# S1_LED_MAT_HDMI.net
KiCad netlist of a schematic drawn in Altium Designer
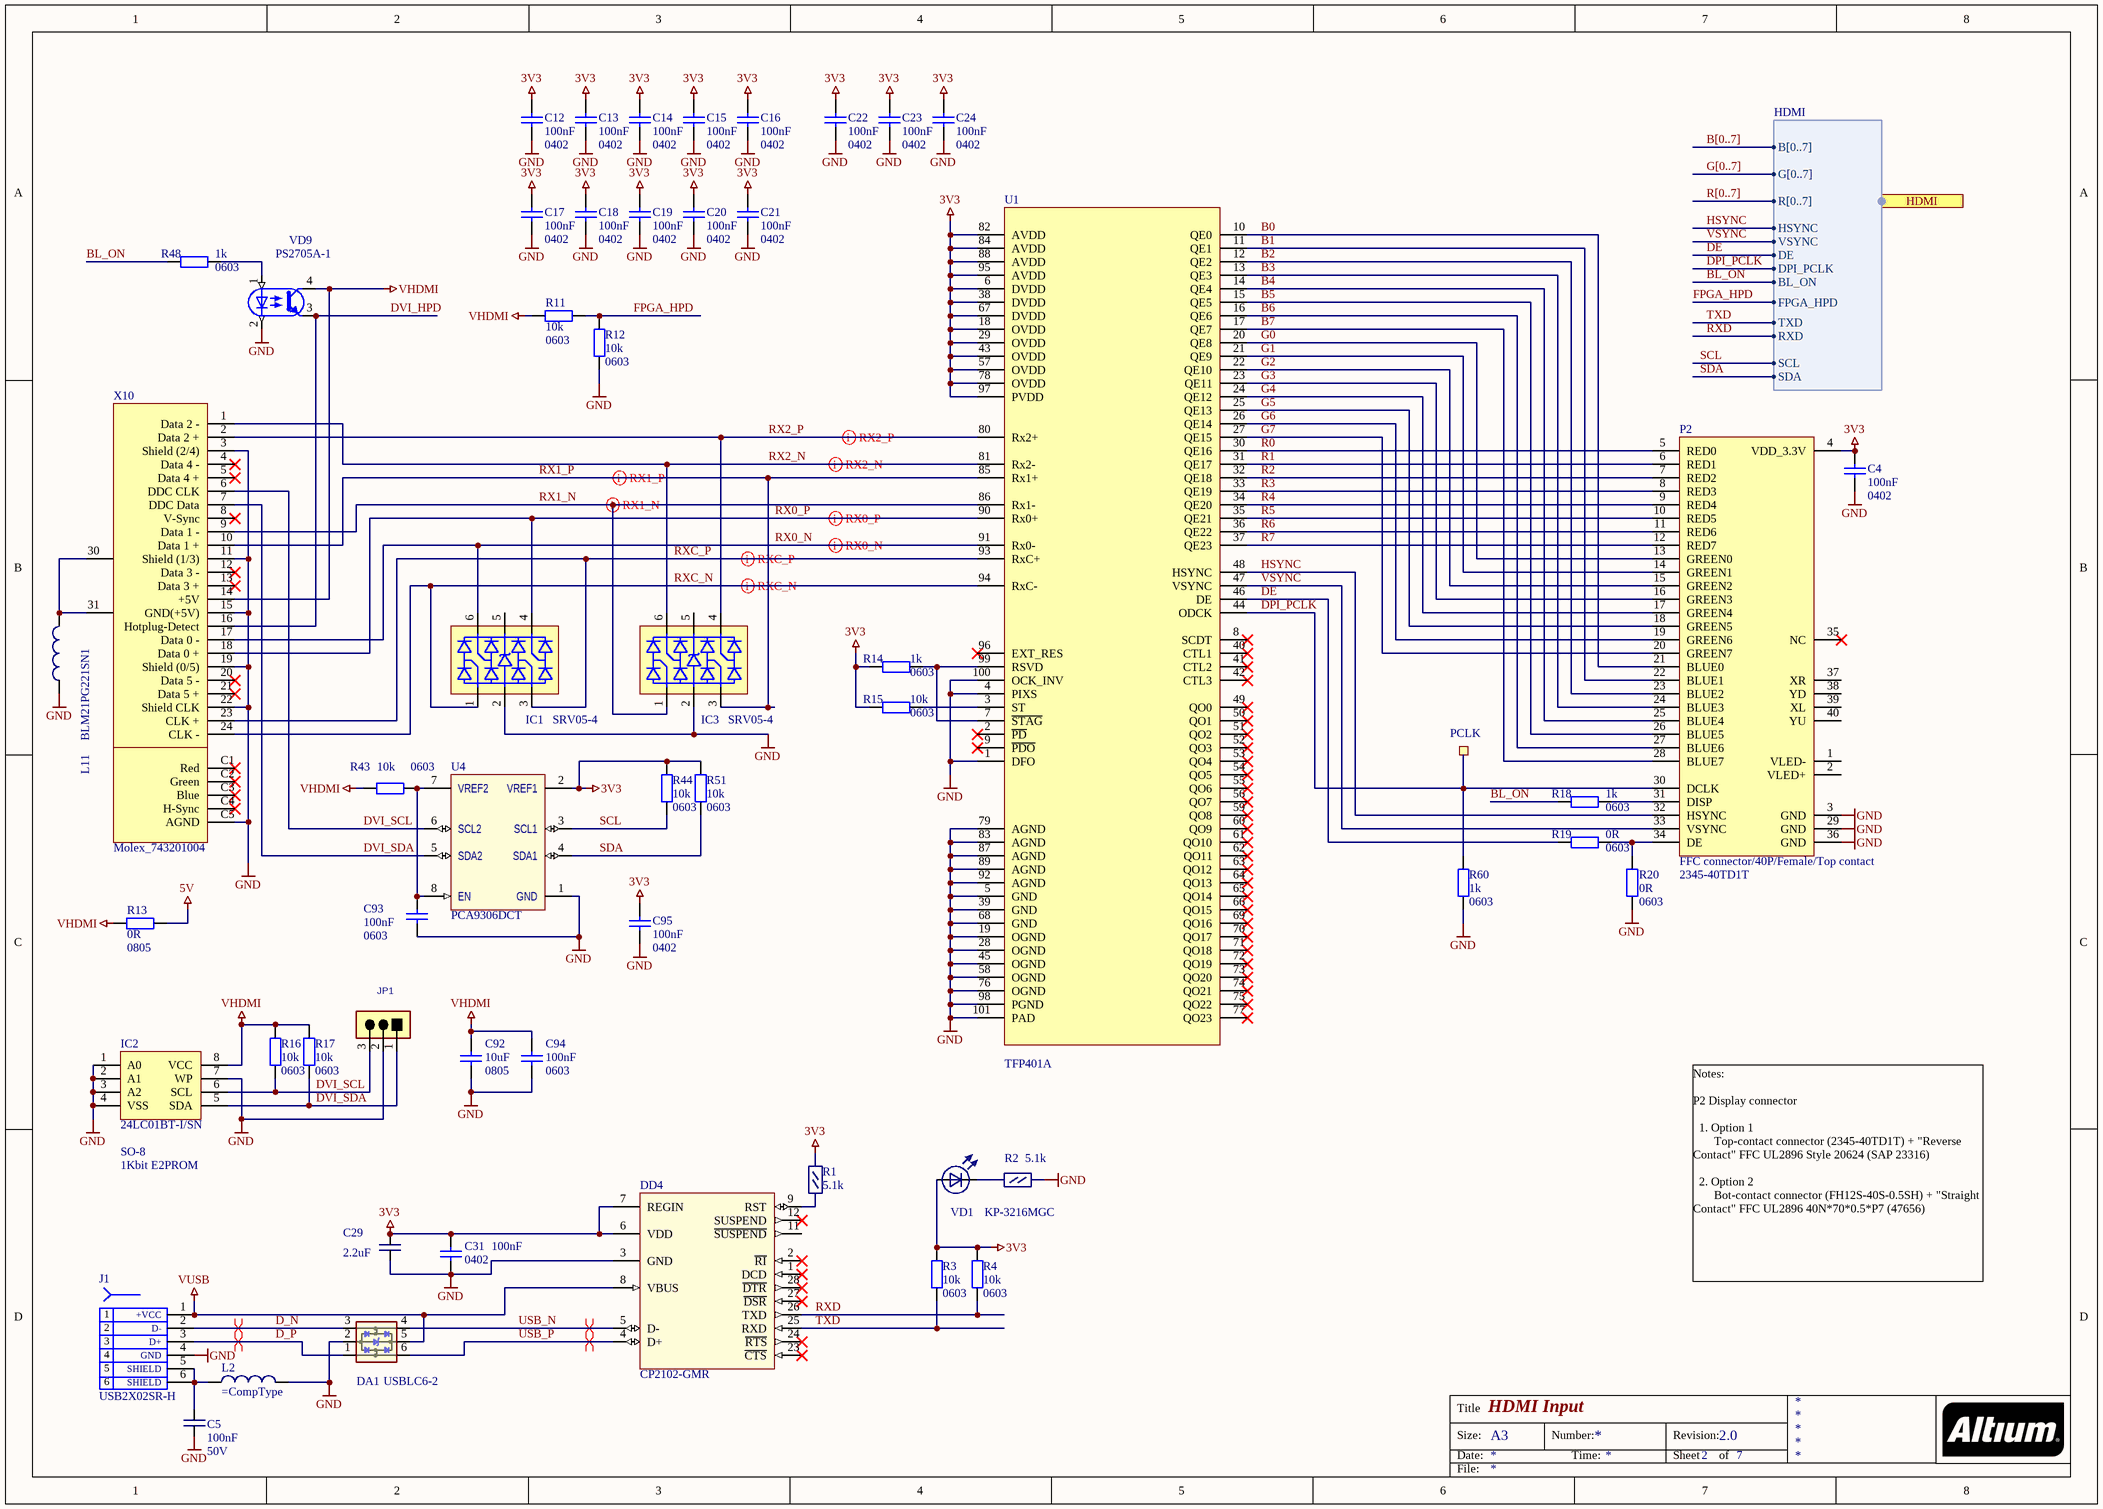
[diagram p0: S1_LED_MAT_HDMI.SCHDOC]

(export (version "E")
  (design (tool "Eeschema 10.0.6"))
  (components
    (comp (ref "C4")
      (value "100nF")
      (footprint "CAPC1005L")
      (description "Capacitor ceramic")
      (fields
        (field (name "MANUFACTURER") "SAMSUNG")
        (field (name "MANUFACTURER PART NUMBER") "CL05B104KO5NNNC")
        (field (name "PACKAGE") "0402")
      )
      (libsource (lib "LED_MAT_3") (part "100nF / 0402 / X7R / 16V"))
    )
    (comp (ref "C5")
      (value "100nF")
      (footprint "CAPC1608L")
      (description "Capacitor SMD")
      (fields
        (field (name "TOLERANCE") "5%")
        (field (name "MANUFACTURER") "SAMSUNG")
        (field (name "VOLTAGE") "50V")
      )
      (libsource (lib "LED_MAT_3") (part "Capacitor CC0805 100nF C0G"))
    )
    (comp (ref "C12")
      (value "100nF")
      (footprint "CAPC1005L")
      (description "Capacitor ceramic")
      (fields
        (field (name "MANUFACTURER") "SAMSUNG")
        (field (name "MANUFACTURER PART NUMBER") "CL05B104KO5NNNC")
        (field (name "PACKAGE") "0402")
      )
      (libsource (lib "LED_MAT_3") (part "100nF / 0402 / X7R / 16V"))
    )
    (comp (ref "C13")
      (value "100nF")
      (footprint "CAPC1005L")
      (description "Capacitor ceramic")
      (fields
        (field (name "MANUFACTURER") "SAMSUNG")
        (field (name "MANUFACTURER PART NUMBER") "CL05B104KO5NNNC")
        (field (name "PACKAGE") "0402")
      )
      (libsource (lib "LED_MAT_3") (part "100nF / 0402 / X7R / 16V"))
    )
    (comp (ref "C14")
      (value "100nF")
      (footprint "CAPC1005L")
      (description "Capacitor ceramic")
      (fields
        (field (name "MANUFACTURER") "SAMSUNG")
        (field (name "MANUFACTURER PART NUMBER") "CL05B104KO5NNNC")
        (field (name "PACKAGE") "0402")
      )
      (libsource (lib "LED_MAT_3") (part "100nF / 0402 / X7R / 16V"))
    )
    (comp (ref "C15")
      (value "100nF")
      (footprint "CAPC1005L")
      (description "Capacitor ceramic")
      (fields
        (field (name "MANUFACTURER") "SAMSUNG")
        (field (name "MANUFACTURER PART NUMBER") "CL05B104KO5NNNC")
        (field (name "PACKAGE") "0402")
      )
      (libsource (lib "LED_MAT_3") (part "100nF / 0402 / X7R / 16V"))
    )
    (comp (ref "C16")
      (value "100nF")
      (footprint "CAPC1005L")
      (description "Capacitor ceramic")
      (fields
        (field (name "MANUFACTURER") "SAMSUNG")
        (field (name "MANUFACTURER PART NUMBER") "CL05B104KO5NNNC")
        (field (name "PACKAGE") "0402")
      )
      (libsource (lib "LED_MAT_3") (part "100nF / 0402 / X7R / 16V"))
    )
    (comp (ref "C17")
      (value "100nF")
      (footprint "CAPC1005L")
      (description "Capacitor ceramic")
      (fields
        (field (name "MANUFACTURER") "SAMSUNG")
        (field (name "MANUFACTURER PART NUMBER") "CL05B104KO5NNNC")
        (field (name "PACKAGE") "0402")
      )
      (libsource (lib "LED_MAT_3") (part "100nF / 0402 / X7R / 16V"))
    )
    (comp (ref "C18")
      (value "100nF")
      (footprint "CAPC1005L")
      (description "Capacitor ceramic")
      (fields
        (field (name "MANUFACTURER") "SAMSUNG")
        (field (name "MANUFACTURER PART NUMBER") "CL05B104KO5NNNC")
        (field (name "PACKAGE") "0402")
      )
      (libsource (lib "LED_MAT_3") (part "100nF / 0402 / X7R / 16V"))
    )
    (comp (ref "C19")
      (value "100nF")
      (footprint "CAPC1005L")
      (description "Capacitor ceramic")
      (fields
        (field (name "MANUFACTURER") "SAMSUNG")
        (field (name "MANUFACTURER PART NUMBER") "CL05B104KO5NNNC")
        (field (name "PACKAGE") "0402")
      )
      (libsource (lib "LED_MAT_3") (part "100nF / 0402 / X7R / 16V"))
    )
    (comp (ref "C20")
      (value "100nF")
      (footprint "CAPC1005L")
      (description "Capacitor ceramic")
      (fields
        (field (name "MANUFACTURER") "SAMSUNG")
        (field (name "MANUFACTURER PART NUMBER") "CL05B104KO5NNNC")
        (field (name "PACKAGE") "0402")
      )
      (libsource (lib "LED_MAT_3") (part "100nF / 0402 / X7R / 16V"))
    )
    (comp (ref "C21")
      (value "100nF")
      (footprint "CAPC1005L")
      (description "Capacitor ceramic")
      (fields
        (field (name "MANUFACTURER") "SAMSUNG")
        (field (name "MANUFACTURER PART NUMBER") "CL05B104KO5NNNC")
        (field (name "PACKAGE") "0402")
      )
      (libsource (lib "LED_MAT_3") (part "100nF / 0402 / X7R / 16V"))
    )
    (comp (ref "C22")
      (value "100nF")
      (footprint "CAPC1005L")
      (description "Capacitor ceramic")
      (fields
        (field (name "MANUFACTURER") "SAMSUNG")
        (field (name "MANUFACTURER PART NUMBER") "CL05B104KO5NNNC")
        (field (name "PACKAGE") "0402")
      )
      (libsource (lib "LED_MAT_3") (part "100nF / 0402 / X7R / 16V"))
    )
    (comp (ref "C23")
      (value "100nF")
      (footprint "CAPC1005L")
      (description "Capacitor ceramic")
      (fields
        (field (name "MANUFACTURER") "SAMSUNG")
        (field (name "MANUFACTURER PART NUMBER") "CL05B104KO5NNNC")
        (field (name "PACKAGE") "0402")
      )
      (libsource (lib "LED_MAT_3") (part "100nF / 0402 / X7R / 16V"))
    )
    (comp (ref "C24")
      (value "100nF")
      (footprint "CAPC1005L")
      (description "Capacitor ceramic")
      (fields
        (field (name "MANUFACTURER") "SAMSUNG")
        (field (name "MANUFACTURER PART NUMBER") "CL05B104KO5NNNC")
        (field (name "PACKAGE") "0402")
      )
      (libsource (lib "LED_MAT_3") (part "100nF / 0402 / X7R / 16V"))
    )
    (comp (ref "C29")
      (value "2.2uF")
      (footprint "CAPC2012L")
      (description "Capacitor SMD")
      (fields (field (name "VOLTAGE") "50V") (field (name "TOLERANCE") "20%"))
      (libsource (lib "LED_MAT_3") (part "Capacitor CC0805 2.2uF X7R"))
    )
    (comp (ref "C31")
      (value "100nF")
      (footprint "CAPC1005L")
      (description "Capacitor ceramic")
      (fields
        (field (name "MANUFACTURER") "SAMSUNG")
        (field (name "MANUFACTURER PART NUMBER") "CL05B104KO5NNNC")
        (field (name "PACKAGE") "0402")
      )
      (libsource (lib "LED_MAT_3") (part "100nF / 0402 / X7R / 16V"))
    )
    (comp (ref "C92")
      (value "10uF")
      (footprint "CAPC2012L")
      (description "Capacitor ceramic")
      (fields
        (field (name "PACKAGE") "0805")
        (field (name "VOLTAGE") "10V")
        (field (name "Comment") "10uF / 0805 /  X5R / 10V")
      )
      (libsource (lib "LED_MAT_3") (part "10uF / 0805 /  X5R / 10V"))
    )
    (comp (ref "C93")
      (value "100nF")
      (footprint "CAPC1608L")
      (description "Capacitor ceramic")
      (fields
        (field (name "PACKAGE") "0603")
        (field (name "VOLTAGE") "16V")
        (field (name "Comment") "100nF / 0603 / X7R / 16V")
      )
      (libsource (lib "LED_MAT_3") (part "100nF / 0603 / X7R / 16V"))
    )
    (comp (ref "C94")
      (value "100nF")
      (footprint "CAPC1608L")
      (description "Capacitor ceramic")
      (fields
        (field (name "PACKAGE") "0603")
        (field (name "VOLTAGE") "16V")
        (field (name "Comment") "100nF / 0603 / X7R / 16V")
      )
      (libsource (lib "LED_MAT_3") (part "100nF / 0603 / X7R / 16V"))
    )
    (comp (ref "C95")
      (value "100nF")
      (footprint "CAPC1005L")
      (description "Capacitor ceramic")
      (fields
        (field (name "MANUFACTURER") "SAMSUNG")
        (field (name "MANUFACTURER PART NUMBER") "CL05B104KO5NNNC")
        (field (name "PACKAGE") "0402")
      )
      (libsource (lib "LED_MAT_3") (part "100nF / 0402 / X7R / 16V"))
    )
    (comp (ref "DA1")
      (value "USBLC6-2")
      (footprint "SOT95P280X110-6L")
      (description "Very low capacitance ESD protection")
      (fields (field (name "MANUFACTURER") "ST") (field (name "MANUFACTURER PART NUMBER") "USBLC6-2SC6"))
      (libsource (lib "LED_MAT_3") (part "EMC_USBLC6-2SC6"))
    )
    (comp (ref "DD4")
      (value "CP2102-GMR")
      (footprint "QFN50P500X500-28V1N")
      (description "USB to UART bridge")
      (fields (field (name "MANUFACTURER") "SILICON"))
      (libsource (lib "LED_MAT_3") (part "CP2102-GM"))
    )
    (comp (ref "IC1")
      (value "SRV05-4")
      (footprint "SOT23-6 (DBV)")
      (description "Low Capacitance Transient Voltage   Suppressors Diode Array")
      (fields (field (name "MANUFACTURER") "SEMTECH") (field (name "MANUFACTURER PART NUMBER") "SRV05-4.TCT"))
      (libsource (lib "LED_MAT_3") (part "SRV05-4.TCT/5V/300W/TVS Diode Array"))
    )
    (comp (ref "IC2")
      (value "1Kbit E2PROM")
      (footprint "SOIC127P600-8N")
      (description "1K I2C Serial EEPROM")
      (fields
        (field (name "MANUFACTURER") "MICROCHIP")
        (field (name "MANUFACTURER PART NUMBER") "24LC01BT-I/SN")
        (field (name "PACKAGE") "SO-8")
        (field (name "Comment") "24LC01B")
      )
      (libsource (lib "LED_MAT_3") (part "24LC01B"))
    )
    (comp (ref "IC3")
      (value "SRV05-4")
      (footprint "SOT23-6 (DBV)")
      (description "Low Capacitance Transient Voltage   Suppressors Diode Array")
      (fields (field (name "MANUFACTURER") "SEMTECH") (field (name "MANUFACTURER PART NUMBER") "SRV05-4.TCT"))
      (libsource (lib "LED_MAT_3") (part "SRV05-4.TCT/5V/300W/TVS Diode Array"))
    )
    (comp (ref "J1")
      (value "USB2X02SR-H")
      (footprint "USB_B")
      (description "USB-B")
      (fields (field (name "MANUFACTURER") "AUK"))
      (libsource (lib "LED_MAT_3") (part "CON6_LEFT"))
    )
    (comp (ref "JP1")
      (value "Header 1x3, 2.54mm")
      (footprint "HDR-1x3 SAP 10347")
      (description "Header, 3-Pin")
      (fields
        (field (name "MANUFACTURER PART NUMBER") "21B1264-03S10-01G-6/3")
        (field (name "MANUFACTURER") "JIH VEI")
      )
      (libsource (lib "LED_MAT_3") (part "HDR-1x3"))
    )
    (comp (ref "L2")
      (value "~")
      (footprint "INDC2012L")
      (description "Ferrite bead")
      (fields
        (field (name "MANUFACTURER") "Murata")
        (field (name "MANUFACTURER PART NUMBER") "BLM21PG221SN1")
      )
      (libsource (lib "LED_MAT_3") (part "INDUCTOR"))
    )
    (comp (ref "L11")
      (value "BLM21PG221SN1")
      (footprint "INDC2012L")
      (description "Ferrite bead")
      (fields (field (name "MANUFACTURER") "Murata"))
      (libsource (lib "LED_MAT_3") (part "L0805_BLM21"))
    )
    (comp (ref "P2")
      (value "FFC connector/40P/Female/Top contact")
      (footprint "OUPIN 2345-40")
      (fields
        (field (name "MANUFACTURER") "OUPIIN")
        (field (name "MANUFACTURER PART NUMBER") "2345-40TD1T")
        (field (name "Comment") "TIANMA_TM043NBH02")
      )
      (libsource (lib "LED_MAT_3") (part "TIANMA_TM043NBH02"))
    )
    (comp (ref "PCLK")
      (value "Ø1.0mm,SMD")
      (footprint "TP_SMD_1MM")
      (description "circular SMD testpad 1mm")
      (libsource (lib "LED_MAT_3") (part "TESTPAD_SMD"))
    )
    (comp (ref "R1")
      (value "5.1k")
      (footprint "RESC1608L")
      (description "Resistor SMD")
      (fields (field (name "TOLERANCE") "5%") (field (name "MANUFACTURER") "YAGEO"))
      (libsource (lib "") (part "Resistor RC0805 5k1_1"))
    )
    (comp (ref "R2")
      (value "5.1k")
      (footprint "RESC1608L")
      (description "Resistor SMD")
      (fields (field (name "TOLERANCE") "5%") (field (name "MANUFACTURER") "YAGEO"))
      (libsource (lib "LED_MAT_3") (part "Resistor RC0805 5k1"))
    )
    (comp (ref "R3")
      (value "10k")
      (footprint "RESC1608L")
      (description "Resistor")
      (fields (field (name "TOLERANCE") "1%") (field (name "PACKAGE") "0603") (field (name "VOLTAGE") "50V"))
      (libsource (lib "LED_MAT_3") (part "10k / 1% / 0603 / TC100 / 50V / 0.1W"))
    )
    (comp (ref "R4")
      (value "10k")
      (footprint "RESC1608L")
      (description "Resistor")
      (fields (field (name "TOLERANCE") "1%") (field (name "PACKAGE") "0603") (field (name "VOLTAGE") "50V"))
      (libsource (lib "LED_MAT_3") (part "10k / 1% / 0603 / TC100 / 50V / 0.1W"))
    )
    (comp (ref "R11")
      (value "10k")
      (footprint "RESC1608L")
      (description "Resistor")
      (fields (field (name "TOLERANCE") "1%") (field (name "PACKAGE") "0603") (field (name "VOLTAGE") "50V"))
      (libsource (lib "") (part "10k / 1% / 0603 / TC100 / 50V / 0.1W_1"))
    )
    (comp (ref "R12")
      (value "10k")
      (footprint "RESC1608L")
      (description "Resistor")
      (fields (field (name "TOLERANCE") "1%") (field (name "PACKAGE") "0603") (field (name "VOLTAGE") "50V"))
      (libsource (lib "LED_MAT_3") (part "10k / 1% / 0603 / TC100 / 50V / 0.1W"))
    )
    (comp (ref "R13")
      (value "0R")
      (footprint "RESC2012L")
      (description "Resistor")
      (fields
        (field (name "MANUFACTURER") "YAGEO")
        (field (name "MANUFACTURER PART NUMBER") "RC0805JR-070RL")
        (field (name "PACKAGE") "0805")
      )
      (libsource (lib "LED_MAT_3") (part "0R / 2A / 0805/ TC100 / 50V / 0.125W"))
    )
    (comp (ref "R14")
      (value "1k")
      (footprint "RESC1608L")
      (description "Resistor")
      (fields (field (name "TOLERANCE") "1%") (field (name "PACKAGE") "0603") (field (name "VOLTAGE") "50V"))
      (libsource (lib "LED_MAT_3") (part "1k / 1% / 0603 / TC100 / 50V / 0.1W"))
    )
    (comp (ref "R15")
      (value "10k")
      (footprint "RESC1608L")
      (description "Resistor")
      (fields (field (name "TOLERANCE") "1%") (field (name "PACKAGE") "0603") (field (name "VOLTAGE") "50V"))
      (libsource (lib "") (part "10k / 1% / 0603 / TC100 / 50V / 0.1W_1"))
    )
    (comp (ref "R16")
      (value "10k")
      (footprint "RESC1608L")
      (description "Resistor")
      (fields (field (name "TOLERANCE") "1%") (field (name "PACKAGE") "0603") (field (name "VOLTAGE") "50V"))
      (libsource (lib "LED_MAT_3") (part "10k / 1% / 0603 / TC100 / 50V / 0.1W"))
    )
    (comp (ref "R17")
      (value "10k")
      (footprint "RESC1608L")
      (description "Resistor")
      (fields (field (name "TOLERANCE") "1%") (field (name "PACKAGE") "0603") (field (name "VOLTAGE") "50V"))
      (libsource (lib "LED_MAT_3") (part "10k / 1% / 0603 / TC100 / 50V / 0.1W"))
    )
    (comp (ref "R18")
      (value "1k")
      (footprint "RESC1608L")
      (description "Resistor")
      (fields (field (name "TOLERANCE") "1%") (field (name "PACKAGE") "0603") (field (name "VOLTAGE") "50V"))
      (libsource (lib "LED_MAT_3") (part "1k / 1% / 0603 / TC100 / 50V / 0.1W"))
    )
    (comp (ref "R19")
      (value "0R")
      (footprint "RESC1608L")
      (description "Resistor")
      (fields
        (field (name "MANUFACTURER") "YAGEO")
        (field (name "MANUFACTURER PART NUMBER") "RC0603FR-070RL")
        (field (name "PACKAGE") "0603")
      )
      (libsource (lib "") (part "0R / 1A / 0603 / TC100 / 50V / 0.1W_1"))
    )
    (comp (ref "R20")
      (value "0R")
      (footprint "RESC1608L")
      (description "Resistor")
      (fields
        (field (name "MANUFACTURER") "YAGEO")
        (field (name "MANUFACTURER PART NUMBER") "RC0603FR-070RL")
        (field (name "PACKAGE") "0603")
      )
      (libsource (lib "LED_MAT_3") (part "0R / 1A / 0603 / TC100 / 50V / 0.1W"))
    )
    (comp (ref "R43")
      (value "10k")
      (footprint "RESC1608L")
      (description "Resistor")
      (fields (field (name "TOLERANCE") "1%") (field (name "PACKAGE") "0603") (field (name "VOLTAGE") "50V"))
      (libsource (lib "") (part "10k / 1% / 0603 / TC100 / 50V / 0.1W_1"))
    )
    (comp (ref "R44")
      (value "10k")
      (footprint "RESC1608L")
      (description "Resistor")
      (fields (field (name "TOLERANCE") "1%") (field (name "PACKAGE") "0603") (field (name "VOLTAGE") "50V"))
      (libsource (lib "LED_MAT_3") (part "10k / 1% / 0603 / TC100 / 50V / 0.1W"))
    )
    (comp (ref "R48")
      (value "1k")
      (footprint "RESC1608L")
      (description "Resistor")
      (fields (field (name "TOLERANCE") "1%") (field (name "PACKAGE") "0603") (field (name "VOLTAGE") "50V"))
      (libsource (lib "LED_MAT_3") (part "1k / 1% / 0603 / TC100 / 50V / 0.1W"))
    )
    (comp (ref "R51")
      (value "10k")
      (footprint "RESC1608L")
      (description "Resistor")
      (fields (field (name "TOLERANCE") "1%") (field (name "PACKAGE") "0603") (field (name "VOLTAGE") "50V"))
      (libsource (lib "LED_MAT_3") (part "10k / 1% / 0603 / TC100 / 50V / 0.1W"))
    )
    (comp (ref "R60")
      (value "1k")
      (footprint "RESC1608L")
      (description "Resistor")
      (fields (field (name "TOLERANCE") "1%") (field (name "PACKAGE") "0603") (field (name "VOLTAGE") "50V"))
      (libsource (lib "") (part "1k / 1% / 0603 / TC100 / 50V / 0.1W_1"))
    )
    (comp (ref "U1")
      (value "TFP401A")
      (footprint "100 LQFP (14x14)")
      (description "PanelBus DVI Receiver 165MHz, HSYNC fix")
      (fields (field (name "MANUFACTURER") "TI") (field (name "MANUFACTURER PART NUMBER") "TFP401A"))
      (libsource (lib "LED_MAT_3") (part "TFP401A_2"))
    )
    (comp (ref "U4")
      (value "PCA9306DCT")
      (footprint "TSSOP65-8L - DCT (R-PDSO-G8)")
      (description "Bidirectional Translator")
      (fields (field (name "MANUFACTURER") "TI"))
      (libsource (lib "LED_MAT_3") (part "PCA9306DCTT"))
    )
    (comp (ref "VD1")
      (value "KP-3216MGC")
      (footprint "LED3216X10L")
      (description "SMD LED GREEN")
      (fields (field (name "MANUFACTURER") "KINGBRIGHT"))
      (libsource (lib "LED_MAT_3") (part "KP-3216MGC"))
    )
    (comp (ref "VD9")
      (value "PS2705A-1")
      (footprint "PS2705A-1")
      (description "Photocoupler, SOP package")
      (fields
        (field (name "MANUFACTURER") "RENESAS")
        (field (name "MANUFACTURER PART NUMBER") "PS2705A-1-F3-A")
      )
      (libsource (lib "LED_MAT_3") (part "PS2701A-1"))
    )
    (comp (ref "X10")
      (value "Molex_743201004")
      (footprint "DVI 29pol / Female Insertion / 90°")
      (description "DVI Connector")
      (fields
        (field (name "MANUFACTURER") "AMTEK")
        (field (name "MANUFACTURER PART NUMBER") "DVIR-F29SWND-L")
      )
      (libsource (lib "LED_MAT_3") (part "DVI / 29pole / 90°"))
    )
  )
  (nets
    (net (code "2") (name "/B0") (class "Default")
      (node (ref "P2") (pin "21") (pinfunction "BLUE0_21") (pintype "passive"))
      (node (ref "U1") (pin "10") (pinfunction "QE0_10") (pintype "passive"))
    )
    (net (code "3") (name "/B1") (class "Default")
      (node (ref "P2") (pin "22") (pinfunction "BLUE1_22") (pintype "passive"))
      (node (ref "U1") (pin "11") (pinfunction "QE1_11") (pintype "passive"))
    )
    (net (code "4") (name "/B2") (class "Default")
      (node (ref "P2") (pin "23") (pinfunction "BLUE2_23") (pintype "passive"))
      (node (ref "U1") (pin "12") (pinfunction "QE2_12") (pintype "passive"))
    )
    (net (code "5") (name "/B3") (class "Default")
      (node (ref "P2") (pin "24") (pinfunction "BLUE3_24") (pintype "passive"))
      (node (ref "U1") (pin "13") (pinfunction "QE3_13") (pintype "passive"))
    )
    (net (code "6") (name "/B4") (class "Default")
      (node (ref "P2") (pin "25") (pinfunction "BLUE4_25") (pintype "passive"))
      (node (ref "U1") (pin "14") (pinfunction "QE4_14") (pintype "passive"))
    )
    (net (code "7") (name "/B5") (class "Default")
      (node (ref "P2") (pin "26") (pinfunction "BLUE5_26") (pintype "passive"))
      (node (ref "U1") (pin "15") (pinfunction "QE5_15") (pintype "passive"))
    )
    (net (code "8") (name "/B6") (class "Default")
      (node (ref "P2") (pin "27") (pinfunction "BLUE6_27") (pintype "passive"))
      (node (ref "U1") (pin "16") (pinfunction "QE6_16") (pintype "passive"))
    )
    (net (code "9") (name "/B7") (class "Default")
      (node (ref "P2") (pin "28") (pinfunction "BLUE7_28") (pintype "passive"))
      (node (ref "U1") (pin "17") (pinfunction "QE7_17") (pintype "passive"))
    )
    (net (code "10") (name "/BL_ON") (class "Default")
      (node (ref "R18") (pin "2") (pinfunction "2_2") (pintype "passive"))
      (node (ref "R48") (pin "2") (pinfunction "2_2") (pintype "passive"))
    )
    (net (code "11") (name "/DE") (class "Default")
      (node (ref "R19") (pin "1") (pinfunction "1_1") (pintype "passive"))
      (node (ref "U1") (pin "46") (pinfunction "DE_46") (pintype "passive"))
    )
    (net (code "12") (name "/DPI_PCLK") (class "Default")
      (node (ref "P2") (pin "30") (pinfunction "DCLK_30") (pintype "passive"))
      (node (ref "PCLK") (pin "1") (pinfunction "1_1") (pintype "passive"))
      (node (ref "R60") (pin "1") (pinfunction "1_1") (pintype "passive"))
      (node (ref "U1") (pin "44") (pinfunction "ODCK_44") (pintype "passive"))
    )
    (net (code "13") (name "/DVI_HPD") (class "Default")
      (node (ref "VD9") (pin "3") (pinfunction "3_3") (pintype "passive"))
      (node (ref "X10") (pin "16") (pinfunction "Hotplug-Detect_16") (pintype "passive"))
    )
    (net (code "14") (name "/DVI_SCL") (class "Default")
      (node (ref "IC2") (pin "6") (pinfunction "SCL_6") (pintype "passive"))
      (node (ref "JP1") (pin "3") (pinfunction "3_3") (pintype "passive"))
      (node (ref "R16") (pin "2") (pinfunction "2_2") (pintype "passive"))
      (node (ref "U4") (pin "6") (pinfunction "SCL2_6") (pintype "bidirectional"))
      (node (ref "X10") (pin "6") (pinfunction "DDC_CLK_6") (pintype "passive"))
    )
    (net (code "15") (name "/DVI_SDA") (class "Default")
      (node (ref "IC2") (pin "5") (pinfunction "SDA_5") (pintype "passive"))
      (node (ref "JP1") (pin "1") (pinfunction "1_1") (pintype "passive"))
      (node (ref "R17") (pin "2") (pinfunction "2_2") (pintype "passive"))
      (node (ref "U4") (pin "5") (pinfunction "SDA2_5") (pintype "bidirectional"))
      (node (ref "X10") (pin "7") (pinfunction "DDC_Data_7") (pintype "passive"))
    )
    (net (code "16") (name "/D_N") (class "Default")
      (node (ref "DA1") (pin "3") (pinfunction "12_3") (pintype "passive"))
      (node (ref "J1") (pin "2") (pinfunction "D-_2") (pintype "passive"))
    )
    (net (code "17") (name "/D_P") (class "Default")
      (node (ref "DA1") (pin "1") (pinfunction "10_1") (pintype "passive"))
      (node (ref "J1") (pin "3") (pinfunction "D+_3") (pintype "passive"))
    )
    (net (code "18") (name "/FPGA_HPD") (class "Default")
      (node (ref "R11") (pin "2") (pinfunction "2_2") (pintype "passive"))
      (node (ref "R12") (pin "1") (pinfunction "1_1") (pintype "passive"))
    )
    (net (code "19") (name "/G0") (class "Default")
      (node (ref "P2") (pin "13") (pinfunction "GREEN0_13") (pintype "passive"))
      (node (ref "U1") (pin "20") (pinfunction "QE8_20") (pintype "passive"))
    )
    (net (code "20") (name "/G1") (class "Default")
      (node (ref "P2") (pin "14") (pinfunction "GREEN1_14") (pintype "passive"))
      (node (ref "U1") (pin "21") (pinfunction "QE9_21") (pintype "passive"))
    )
    (net (code "21") (name "/G2") (class "Default")
      (node (ref "P2") (pin "15") (pinfunction "GREEN2_15") (pintype "passive"))
      (node (ref "U1") (pin "22") (pinfunction "QE10_22") (pintype "passive"))
    )
    (net (code "22") (name "/G3") (class "Default")
      (node (ref "P2") (pin "16") (pinfunction "GREEN3_16") (pintype "passive"))
      (node (ref "U1") (pin "23") (pinfunction "QE11_23") (pintype "passive"))
    )
    (net (code "23") (name "/G4") (class "Default")
      (node (ref "P2") (pin "17") (pinfunction "GREEN4_17") (pintype "passive"))
      (node (ref "U1") (pin "24") (pinfunction "QE12_24") (pintype "passive"))
    )
    (net (code "24") (name "/G5") (class "Default")
      (node (ref "P2") (pin "18") (pinfunction "GREEN5_18") (pintype "passive"))
      (node (ref "U1") (pin "25") (pinfunction "QE13_25") (pintype "passive"))
    )
    (net (code "25") (name "/G6") (class "Default")
      (node (ref "P2") (pin "19") (pinfunction "GREEN6_19") (pintype "passive"))
      (node (ref "U1") (pin "26") (pinfunction "QE14_26") (pintype "passive"))
    )
    (net (code "26") (name "/G7") (class "Default")
      (node (ref "P2") (pin "20") (pinfunction "GREEN7_20") (pintype "passive"))
      (node (ref "U1") (pin "27") (pinfunction "QE15_27") (pintype "passive"))
    )
    (net (code "29") (name "/HSYNC") (class "Default")
      (node (ref "P2") (pin "32") (pinfunction "HSYNC_32") (pintype "passive"))
      (node (ref "U1") (pin "48") (pinfunction "HSYNC_48") (pintype "passive"))
    )
    (net (code "30") (name "/R0") (class "Default")
      (node (ref "P2") (pin "5") (pinfunction "RED0_5") (pintype "passive"))
      (node (ref "U1") (pin "30") (pinfunction "QE16_30") (pintype "passive"))
    )
    (net (code "31") (name "/R1") (class "Default")
      (node (ref "P2") (pin "6") (pinfunction "RED1_6") (pintype "passive"))
      (node (ref "U1") (pin "31") (pinfunction "QE17_31") (pintype "passive"))
    )
    (net (code "32") (name "/R2") (class "Default")
      (node (ref "P2") (pin "7") (pinfunction "RED2_7") (pintype "passive"))
      (node (ref "U1") (pin "32") (pinfunction "QE18_32") (pintype "passive"))
    )
    (net (code "33") (name "/R3") (class "Default")
      (node (ref "P2") (pin "8") (pinfunction "RED3_8") (pintype "passive"))
      (node (ref "U1") (pin "33") (pinfunction "QE19_33") (pintype "passive"))
    )
    (net (code "34") (name "/R4") (class "Default")
      (node (ref "P2") (pin "9") (pinfunction "RED4_9") (pintype "passive"))
      (node (ref "U1") (pin "34") (pinfunction "QE20_34") (pintype "passive"))
    )
    (net (code "35") (name "/R5") (class "Default")
      (node (ref "P2") (pin "10") (pinfunction "RED5_10") (pintype "passive"))
      (node (ref "U1") (pin "35") (pinfunction "QE21_35") (pintype "passive"))
    )
    (net (code "36") (name "/R6") (class "Default")
      (node (ref "P2") (pin "11") (pinfunction "RED6_11") (pintype "passive"))
      (node (ref "U1") (pin "36") (pinfunction "QE22_36") (pintype "passive"))
    )
    (net (code "37") (name "/R7") (class "Default")
      (node (ref "P2") (pin "12") (pinfunction "RED7_12") (pintype "passive"))
      (node (ref "U1") (pin "37") (pinfunction "QE23_37") (pintype "passive"))
    )
    (net (code "38") (name "/RX0_N") (class "Default")
      (node (ref "IC1") (pin "6") (pinfunction "6_6") (pintype "passive"))
      (node (ref "U1") (pin "91") (pinfunction "Rx0-_91") (pintype "passive"))
      (node (ref "X10") (pin "17") (pinfunction "Data_0_-_17") (pintype "passive"))
    )
    (net (code "39") (name "/RX0_P") (class "Default")
      (node (ref "IC1") (pin "4") (pinfunction "4_4") (pintype "passive"))
      (node (ref "U1") (pin "90") (pinfunction "Rx0+_90") (pintype "passive"))
      (node (ref "X10") (pin "18") (pinfunction "Data_0_+_18") (pintype "passive"))
    )
    (net (code "40") (name "/RX1_N") (class "Default")
      (node (ref "IC3") (pin "1") (pinfunction "VCC_1") (pintype "passive"))
      (node (ref "U1") (pin "86") (pinfunction "Rx1-_86") (pintype "passive"))
      (node (ref "X10") (pin "9") (pinfunction "Data_1_-_9") (pintype "passive"))
    )
    (net (code "41") (name "/RX1_P") (class "Default")
      (node (ref "IC3") (pin "3") (pinfunction "3_3") (pintype "passive"))
      (node (ref "U1") (pin "85") (pinfunction "Rx1+_85") (pintype "passive"))
      (node (ref "X10") (pin "10") (pinfunction "Data_1_+_10") (pintype "passive"))
    )
    (net (code "42") (name "/RX2_N") (class "Default")
      (node (ref "IC3") (pin "6") (pinfunction "6_6") (pintype "passive"))
      (node (ref "U1") (pin "81") (pinfunction "Rx2-_81") (pintype "passive"))
      (node (ref "X10") (pin "1") (pinfunction "Data_2_-_1") (pintype "passive"))
    )
    (net (code "43") (name "/RX2_P") (class "Default")
      (node (ref "IC3") (pin "4") (pinfunction "4_4") (pintype "passive"))
      (node (ref "U1") (pin "80") (pinfunction "Rx2+_80") (pintype "passive"))
      (node (ref "X10") (pin "2") (pinfunction "Data_2_+_2") (pintype "passive"))
    )
    (net (code "44") (name "/RXC_N") (class "Default")
      (node (ref "IC1") (pin "1") (pinfunction "VCC_1") (pintype "passive"))
      (node (ref "U1") (pin "94") (pinfunction "RxC-_94") (pintype "passive"))
      (node (ref "X10") (pin "24") (pinfunction "CLK_-_24") (pintype "passive"))
    )
    (net (code "45") (name "/RXC_P") (class "Default")
      (node (ref "IC1") (pin "3") (pinfunction "3_3") (pintype "passive"))
      (node (ref "U1") (pin "93") (pinfunction "RxC+_93") (pintype "passive"))
      (node (ref "X10") (pin "23") (pinfunction "CLK_+_23") (pintype "passive"))
    )
    (net (code "46") (name "/RXD") (class "Default")
      (node (ref "DD4") (pin "26") (pinfunction "TXD_26") (pintype "output"))
      (node (ref "R4") (pin "2") (pinfunction "2_2") (pintype "passive"))
    )
    (net (code "48") (name "/SCL") (class "Default")
      (node (ref "R44") (pin "2") (pinfunction "2_2") (pintype "passive"))
      (node (ref "U4") (pin "3") (pinfunction "SCL1_3") (pintype "bidirectional"))
    )
    (net (code "49") (name "/SDA") (class "Default")
      (node (ref "R51") (pin "2") (pinfunction "2_2") (pintype "passive"))
      (node (ref "U4") (pin "4") (pinfunction "SDA1_4") (pintype "bidirectional"))
    )
    (net (code "50") (name "/TXD") (class "Default")
      (node (ref "DD4") (pin "25") (pinfunction "RXD_25") (pintype "input"))
      (node (ref "R3") (pin "2") (pinfunction "2_2") (pintype "passive"))
    )
    (net (code "51") (name "/USB_N") (class "Default")
      (node (ref "DA1") (pin "4") (pinfunction "13_4") (pintype "passive"))
      (node (ref "DD4") (pin "5") (pinfunction "D-_5") (pintype "bidirectional"))
    )
    (net (code "52") (name "/USB_P") (class "Default")
      (node (ref "DA1") (pin "6") (pinfunction "15_6") (pintype "passive"))
      (node (ref "DD4") (pin "4") (pinfunction "D+_4") (pintype "bidirectional"))
    )
    (net (code "53") (name "/VSYNC") (class "Default")
      (node (ref "P2") (pin "33") (pinfunction "VSYNC_33") (pintype "passive"))
      (node (ref "U1") (pin "47") (pinfunction "VSYNC_47") (pintype "passive"))
    )
    (net (code "55") (name "3V3") (class "Default")
      (node (ref "C12") (pin "2") (pinfunction "2_2") (pintype "passive"))
      (node (ref "C13") (pin "2") (pinfunction "2_2") (pintype "passive"))
      (node (ref "C14") (pin "2") (pinfunction "2_2") (pintype "passive"))
      (node (ref "C15") (pin "2") (pinfunction "2_2") (pintype "passive"))
      (node (ref "C16") (pin "2") (pinfunction "2_2") (pintype "passive"))
      (node (ref "C17") (pin "2") (pinfunction "2_2") (pintype "passive"))
      (node (ref "C18") (pin "2") (pinfunction "2_2") (pintype "passive"))
      (node (ref "C19") (pin "2") (pinfunction "2_2") (pintype "passive"))
      (node (ref "C20") (pin "2") (pinfunction "2_2") (pintype "passive"))
      (node (ref "C21") (pin "2") (pinfunction "2_2") (pintype "passive"))
      (node (ref "C22") (pin "2") (pinfunction "2_2") (pintype "passive"))
      (node (ref "C23") (pin "2") (pinfunction "2_2") (pintype "passive"))
      (node (ref "C24") (pin "2") (pinfunction "2_2") (pintype "passive"))
      (node (ref "C29") (pin "1") (pintype "passive"))
      (node (ref "C31") (pin "2") (pinfunction "2_2") (pintype "passive"))
      (node (ref "C4") (pin "2") (pinfunction "2_2") (pintype "passive"))
      (node (ref "C95") (pin "2") (pinfunction "2_2") (pintype "passive"))
      (node (ref "DD4") (pin "6") (pinfunction "VDD_6") (pintype "power_in"))
      (node (ref "DD4") (pin "7") (pinfunction "REGIN_7") (pintype "power_in"))
      (node (ref "P2") (pin "4") (pinfunction "VDD_3.3V_4") (pintype "passive"))
      (node (ref "R1") (pin "1") (pinfunction "1_1") (pintype "passive"))
      (node (ref "R14") (pin "2") (pinfunction "2_2") (pintype "passive"))
      (node (ref "R15") (pin "1") (pinfunction "1_1") (pintype "passive"))
      (node (ref "R3") (pin "1") (pinfunction "1_1") (pintype "passive"))
      (node (ref "R4") (pin "1") (pinfunction "1_1") (pintype "passive"))
      (node (ref "R44") (pin "1") (pinfunction "1_1") (pintype "passive"))
      (node (ref "R51") (pin "1") (pinfunction "1_1") (pintype "passive"))
      (node (ref "U1") (pin "18") (pinfunction "OVDD_18") (pintype "passive"))
      (node (ref "U1") (pin "29") (pinfunction "OVDD_29") (pintype "passive"))
      (node (ref "U1") (pin "38") (pinfunction "DVDD_38") (pintype "passive"))
      (node (ref "U1") (pin "43") (pinfunction "OVDD_43") (pintype "passive"))
      (node (ref "U1") (pin "57") (pinfunction "OVDD_57") (pintype "passive"))
      (node (ref "U1") (pin "6") (pinfunction "DVDD_6") (pintype "passive"))
      (node (ref "U1") (pin "67") (pinfunction "DVDD_67") (pintype "passive"))
      (node (ref "U1") (pin "78") (pinfunction "OVDD_78") (pintype "passive"))
      (node (ref "U1") (pin "82") (pinfunction "AVDD_82") (pintype "passive"))
      (node (ref "U1") (pin "84") (pinfunction "AVDD_84") (pintype "passive"))
      (node (ref "U1") (pin "88") (pinfunction "AVDD_88") (pintype "passive"))
      (node (ref "U1") (pin "95") (pinfunction "AVDD_95") (pintype "passive"))
      (node (ref "U1") (pin "97") (pinfunction "PVDD_97") (pintype "passive"))
      (node (ref "U4") (pin "2") (pinfunction "VREF1_2") (pintype "power_in"))
      (node (ref "VD1") (pin "1") (pinfunction "1_1") (pintype "passive"))
    )
    (net (code "56") (name "5V") (class "Default")
      (node (ref "R13") (pin "1") (pinfunction "1_1") (pintype "passive"))
    )
    (net (code "57") (name "GND") (class "Default")
      (node (ref "C12") (pin "1") (pinfunction "1_1") (pintype "passive"))
      (node (ref "C13") (pin "1") (pinfunction "1_1") (pintype "passive"))
      (node (ref "C14") (pin "1") (pinfunction "1_1") (pintype "passive"))
      (node (ref "C15") (pin "1") (pinfunction "1_1") (pintype "passive"))
      (node (ref "C16") (pin "1") (pinfunction "1_1") (pintype "passive"))
      (node (ref "C17") (pin "1") (pinfunction "1_1") (pintype "passive"))
      (node (ref "C18") (pin "1") (pinfunction "1_1") (pintype "passive"))
      (node (ref "C19") (pin "1") (pinfunction "1_1") (pintype "passive"))
      (node (ref "C20") (pin "1") (pinfunction "1_1") (pintype "passive"))
      (node (ref "C21") (pin "1") (pinfunction "1_1") (pintype "passive"))
      (node (ref "C22") (pin "1") (pinfunction "1_1") (pintype "passive"))
      (node (ref "C23") (pin "1") (pinfunction "1_1") (pintype "passive"))
      (node (ref "C24") (pin "1") (pinfunction "1_1") (pintype "passive"))
      (node (ref "C29") (pin "2") (pintype "passive"))
      (node (ref "C31") (pin "1") (pinfunction "1_1") (pintype "passive"))
      (node (ref "C4") (pin "1") (pinfunction "1_1") (pintype "passive"))
      (node (ref "C5") (pin "2") (pintype "passive"))
      (node (ref "C92") (pin "2") (pinfunction "2_2") (pintype "passive"))
      (node (ref "C93") (pin "1") (pinfunction "1_1") (pintype "passive"))
      (node (ref "C94") (pin "1") (pinfunction "1_1") (pintype "passive"))
      (node (ref "C95") (pin "1") (pinfunction "1_1") (pintype "passive"))
      (node (ref "DA1") (pin "2") (pinfunction "11_2") (pintype "passive"))
      (node (ref "DD4") (pin "29") (pinfunction "GND_29") (pintype "power_in"))
      (node (ref "DD4") (pin "3") (pinfunction "GND_3") (pintype "power_in"))
      (node (ref "IC1") (pin "2") (pinfunction "2_2") (pintype "passive"))
      (node (ref "IC2") (pin "1") (pinfunction "A0_1") (pintype "passive"))
      (node (ref "IC2") (pin "2") (pinfunction "A1_2") (pintype "passive"))
      (node (ref "IC2") (pin "3") (pinfunction "A2_3") (pintype "passive"))
      (node (ref "IC2") (pin "4") (pinfunction "VSS_4") (pintype "passive"))
      (node (ref "IC2") (pin "7") (pinfunction "WP_7") (pintype "passive"))
      (node (ref "IC3") (pin "2") (pinfunction "2_2") (pintype "passive"))
      (node (ref "J1") (pin "4") (pinfunction "GND_4") (pintype "passive"))
      (node (ref "JP1") (pin "2") (pinfunction "2_2") (pintype "passive"))
      (node (ref "L11") (pin "1") (pinfunction "1_1") (pintype "passive"))
      (node (ref "L2") (pin "2") (pinfunction "2_2") (pintype "passive"))
      (node (ref "P2") (pin "0") (pinfunction "GND_0") (pintype "power_in"))
      (node (ref "P2") (pin "29") (pinfunction "GND_29") (pintype "passive"))
      (node (ref "P2") (pin "3") (pinfunction "GND_3") (pintype "passive"))
      (node (ref "P2") (pin "36") (pinfunction "GND_36") (pintype "passive"))
      (node (ref "R12") (pin "2") (pinfunction "2_2") (pintype "passive"))
      (node (ref "R2") (pin "1") (pinfunction "1_1") (pintype "passive"))
      (node (ref "R20") (pin "1") (pinfunction "1_1") (pintype "passive"))
      (node (ref "R60") (pin "2") (pinfunction "2_2") (pintype "passive"))
      (node (ref "U1") (pin "1") (pinfunction "DFO_1") (pintype "passive"))
      (node (ref "U1") (pin "100") (pinfunction "OCK_INV_100") (pintype "passive"))
      (node (ref "U1") (pin "101") (pinfunction "PAD_101") (pintype "passive"))
      (node (ref "U1") (pin "19") (pinfunction "OGND_19") (pintype "passive"))
      (node (ref "U1") (pin "28") (pinfunction "OGND_28") (pintype "passive"))
      (node (ref "U1") (pin "39") (pinfunction "GND_39") (pintype "passive"))
      (node (ref "U1") (pin "4") (pinfunction "PIXS_4") (pintype "passive"))
      (node (ref "U1") (pin "45") (pinfunction "OGND_45") (pintype "passive"))
      (node (ref "U1") (pin "5") (pinfunction "GND_5") (pintype "passive"))
      (node (ref "U1") (pin "58") (pinfunction "OGND_58") (pintype "passive"))
      (node (ref "U1") (pin "68") (pinfunction "GND_68") (pintype "passive"))
      (node (ref "U1") (pin "76") (pinfunction "OGND_76") (pintype "passive"))
      (node (ref "U1") (pin "79") (pinfunction "AGND_79") (pintype "passive"))
      (node (ref "U1") (pin "83") (pinfunction "AGND_83") (pintype "passive"))
      (node (ref "U1") (pin "87") (pinfunction "AGND_87") (pintype "passive"))
      (node (ref "U1") (pin "89") (pinfunction "AGND_89") (pintype "passive"))
      (node (ref "U1") (pin "92") (pinfunction "AGND_92") (pintype "passive"))
      (node (ref "U1") (pin "98") (pinfunction "PGND_98") (pintype "passive"))
      (node (ref "U4") (pin "1") (pinfunction "GND_1") (pintype "power_in"))
      (node (ref "VD9") (pin "2") (pinfunction "K_2") (pintype "output"))
      (node (ref "X10") (pin "11") (pinfunction "Shield_(1/3)_11") (pintype "passive"))
      (node (ref "X10") (pin "15") (pinfunction "GND(+5V)_15") (pintype "passive"))
      (node (ref "X10") (pin "19") (pinfunction "Shield_(0/5)_19") (pintype "passive"))
      (node (ref "X10") (pin "22") (pinfunction "Shield_CLK_22") (pintype "passive"))
      (node (ref "X10") (pin "3") (pinfunction "Shield_(2/4)_3") (pintype "passive"))
      (node (ref "X10") (pin "C5") (pinfunction "AGND_C5") (pintype "passive"))
    )
    (net (code "58") (name "Net-(C5-Pad1)") (class "Default")
      (node (ref "C5") (pin "1") (pintype "passive"))
      (node (ref "J1") (pin "5") (pinfunction "SHIELD_5") (pintype "passive"))
      (node (ref "J1") (pin "6") (pinfunction "SHIELD_6") (pintype "passive"))
      (node (ref "L2") (pin "1") (pinfunction "1_1") (pintype "passive"))
    )
    (net (code "59") (name "Net-(DD4-RST)") (class "Default")
      (node (ref "DD4") (pin "9") (pinfunction "RST_9") (pintype "bidirectional"))
      (node (ref "R1") (pin "2") (pinfunction "2_2") (pintype "passive"))
    )
    (net (code "60") (name "Net-(L11-Pad2)") (class "Default")
      (node (ref "L11") (pin "2") (pinfunction "2_2") (pintype "passive"))
      (node (ref "X10") (pin "30") (pintype "passive"))
      (node (ref "X10") (pin "31") (pintype "passive"))
    )
    (net (code "61") (name "Net-(P2-DE)") (class "Default")
      (node (ref "P2") (pin "34") (pinfunction "DE_34") (pintype "passive"))
      (node (ref "R19") (pin "2") (pinfunction "2_2") (pintype "passive"))
      (node (ref "R20") (pin "2") (pinfunction "2_2") (pintype "passive"))
    )
    (net (code "62") (name "Net-(P2-DISP)") (class "Default")
      (node (ref "P2") (pin "31") (pinfunction "DISP_31") (pintype "passive"))
      (node (ref "R18") (pin "1") (pinfunction "1_1") (pintype "passive"))
    )
    (net (code "63") (name "Net-(R2-Pad2)") (class "Default")
      (node (ref "R2") (pin "2") (pinfunction "2_2") (pintype "passive"))
      (node (ref "VD1") (pin "2") (pinfunction "2_2") (pintype "passive"))
    )
    (net (code "64") (name "Net-(U1-RSVD)") (class "Default")
      (node (ref "R14") (pin "1") (pinfunction "1_1") (pintype "passive"))
      (node (ref "U1") (pin "7") (pinfunction "~{STAG}_7") (pintype "passive"))
      (node (ref "U1") (pin "99") (pinfunction "RSVD_99") (pintype "passive"))
    )
    (net (code "65") (name "Net-(U1-ST)") (class "Default")
      (node (ref "R15") (pin "2") (pinfunction "2_2") (pintype "passive"))
      (node (ref "U1") (pin "3") (pinfunction "ST_3") (pintype "passive"))
    )
    (net (code "66") (name "Net-(U4-EN)") (class "Default")
      (node (ref "C93") (pin "2") (pinfunction "2_2") (pintype "passive"))
      (node (ref "R43") (pin "2") (pinfunction "2_2") (pintype "passive"))
      (node (ref "U4") (pin "7") (pinfunction "VREF2_7") (pintype "power_in"))
      (node (ref "U4") (pin "8") (pinfunction "EN_8") (pintype "input"))
    )
    (net (code "67") (name "Net-(VD9-A)") (class "Default")
      (node (ref "R48") (pin "1") (pinfunction "1_1") (pintype "passive"))
      (node (ref "VD9") (pin "1") (pinfunction "A_1") (pintype "input"))
    )
    (net (code "68") (name "VHDMI") (class "Default")
      (node (ref "C92") (pin "1") (pinfunction "1_1") (pintype "passive"))
      (node (ref "C94") (pin "2") (pinfunction "2_2") (pintype "passive"))
      (node (ref "IC2") (pin "8") (pinfunction "VCC_8") (pintype "passive"))
      (node (ref "R11") (pin "1") (pinfunction "1_1") (pintype "passive"))
      (node (ref "R13") (pin "2") (pinfunction "2_2") (pintype "passive"))
      (node (ref "R16") (pin "1") (pinfunction "1_1") (pintype "passive"))
      (node (ref "R17") (pin "1") (pinfunction "1_1") (pintype "passive"))
      (node (ref "R43") (pin "1") (pinfunction "1_1") (pintype "passive"))
      (node (ref "VD9") (pin "4") (pinfunction "4_4") (pintype "passive"))
      (node (ref "X10") (pin "14") (pinfunction "+5V_14") (pintype "passive"))
    )
    (net (code "69") (name "VUSB") (class "Default")
      (node (ref "DA1") (pin "5") (pinfunction "14_5") (pintype "passive"))
      (node (ref "DD4") (pin "8") (pinfunction "VBUS_8") (pintype "input"))
      (node (ref "J1") (pin "1") (pinfunction "+VCC_1") (pintype "passive"))
    )
    (net (code "70") (name "unconnected-(DD4-DCD-Pad1)") (class "Default")
      (node (ref "DD4") (pin "1") (pinfunction "DCD_1") (pintype "input+no_connect"))
    )
    (net (code "71") (name "unconnected-(DD4-NC-Pad10)") (class "Default")
      (node (ref "DD4") (pin "10") (pinfunction "NC_10") (pintype "passive"))
    )
    (net (code "72") (name "unconnected-(DD4-NC-Pad13)") (class "Default")
      (node (ref "DD4") (pin "13") (pinfunction "NC_13") (pintype "passive"))
    )
    (net (code "73") (name "unconnected-(DD4-NC-Pad14)") (class "Default")
      (node (ref "DD4") (pin "14") (pinfunction "NC_14") (pintype "passive"))
    )
    (net (code "74") (name "unconnected-(DD4-NC-Pad15)") (class "Default")
      (node (ref "DD4") (pin "15") (pinfunction "NC_15") (pintype "passive"))
    )
    (net (code "75") (name "unconnected-(DD4-NC-Pad16)") (class "Default")
      (node (ref "DD4") (pin "16") (pinfunction "NC_16") (pintype "passive"))
    )
    (net (code "76") (name "unconnected-(DD4-NC-Pad17)") (class "Default")
      (node (ref "DD4") (pin "17") (pinfunction "NC_17") (pintype "passive"))
    )
    (net (code "77") (name "unconnected-(DD4-NC-Pad18)") (class "Default")
      (node (ref "DD4") (pin "18") (pinfunction "NC_18") (pintype "passive"))
    )
    (net (code "78") (name "unconnected-(DD4-NC-Pad19)") (class "Default")
      (node (ref "DD4") (pin "19") (pinfunction "NC_19") (pintype "passive"))
    )
    (net (code "79") (name "unconnected-(DD4-NC-Pad20)") (class "Default")
      (node (ref "DD4") (pin "20") (pinfunction "NC_20") (pintype "passive"))
    )
    (net (code "80") (name "unconnected-(DD4-NC-Pad21)") (class "Default")
      (node (ref "DD4") (pin "21") (pinfunction "NC_21") (pintype "passive"))
    )
    (net (code "81") (name "unconnected-(DD4-NC-Pad22)") (class "Default")
      (node (ref "DD4") (pin "22") (pinfunction "NC_22") (pintype "passive"))
    )
    (net (code "82") (name "unconnected-(DD4-SUSPEND-Pad12)") (class "Default")
      (node (ref "DD4") (pin "12") (pinfunction "SUSPEND_12") (pintype "output+no_connect"))
    )
    (net (code "83") (name "unconnected-(DD4-~{CTS}-Pad23)") (class "Default")
      (node (ref "DD4") (pin "23") (pinfunction "~{CTS}_23") (pintype "input+no_connect"))
    )
    (net (code "84") (name "unconnected-(DD4-~{DSR}-Pad27)") (class "Default")
      (node (ref "DD4") (pin "27") (pinfunction "~{DSR}_27") (pintype "input+no_connect"))
    )
    (net (code "85") (name "unconnected-(DD4-~{DTR}-Pad28)") (class "Default")
      (node (ref "DD4") (pin "28") (pinfunction "~{DTR}_28") (pintype "output+no_connect"))
    )
    (net (code "86") (name "unconnected-(DD4-~{RI}-Pad2)") (class "Default")
      (node (ref "DD4") (pin "2") (pinfunction "~{RI}_2") (pintype "input+no_connect"))
    )
    (net (code "87") (name "unconnected-(DD4-~{RTS}-Pad24)") (class "Default")
      (node (ref "DD4") (pin "24") (pinfunction "~{RTS}_24") (pintype "output+no_connect"))
    )
    (net (code "88") (name "unconnected-(DD4-~{SUSPEND}-Pad11)") (class "Default")
      (node (ref "DD4") (pin "11") (pinfunction "~{SUSPEND}_11") (pintype "output"))
    )
    (net (code "89") (name "unconnected-(IC1-Pad5)") (class "Default")
      (node (ref "IC1") (pin "5") (pinfunction "5_5") (pintype "passive"))
    )
    (net (code "90") (name "unconnected-(IC3-Pad5)") (class "Default")
      (node (ref "IC3") (pin "5") (pinfunction "5_5") (pintype "passive"))
    )
    (net (code "91") (name "unconnected-(P2-NC-Pad35)") (class "Default")
      (node (ref "P2") (pin "35") (pinfunction "NC_35") (pintype "passive+no_connect"))
    )
    (net (code "92") (name "unconnected-(P2-VLED+-Pad2)") (class "Default")
      (node (ref "P2") (pin "2") (pinfunction "VLED+_2") (pintype "passive"))
    )
    (net (code "93") (name "unconnected-(P2-VLED--Pad1)") (class "Default")
      (node (ref "P2") (pin "1") (pinfunction "VLED-_1") (pintype "passive"))
    )
    (net (code "94") (name "unconnected-(P2-XL-Pad39)") (class "Default")
      (node (ref "P2") (pin "39") (pinfunction "XL_39") (pintype "passive"))
    )
    (net (code "95") (name "unconnected-(P2-XR-Pad37)") (class "Default")
      (node (ref "P2") (pin "37") (pinfunction "XR_37") (pintype "passive"))
    )
    (net (code "96") (name "unconnected-(P2-YD-Pad38)") (class "Default")
      (node (ref "P2") (pin "38") (pinfunction "YD_38") (pintype "passive"))
    )
    (net (code "97") (name "unconnected-(P2-YU-Pad40)") (class "Default")
      (node (ref "P2") (pin "40") (pinfunction "YU_40") (pintype "passive"))
    )
    (net (code "98") (name "unconnected-(U1-CTL1-Pad40)") (class "Default")
      (node (ref "U1") (pin "40") (pinfunction "CTL1_40") (pintype "passive+no_connect"))
    )
    (net (code "99") (name "unconnected-(U1-CTL2-Pad41)") (class "Default")
      (node (ref "U1") (pin "41") (pinfunction "CTL2_41") (pintype "passive+no_connect"))
    )
    (net (code "100") (name "unconnected-(U1-CTL3-Pad42)") (class "Default")
      (node (ref "U1") (pin "42") (pinfunction "CTL3_42") (pintype "passive+no_connect"))
    )
    (net (code "101") (name "unconnected-(U1-EXT_RES-Pad96)") (class "Default")
      (node (ref "U1") (pin "96") (pinfunction "EXT_RES_96") (pintype "passive+no_connect"))
    )
    (net (code "102") (name "unconnected-(U1-QO0-Pad49)") (class "Default")
      (node (ref "U1") (pin "49") (pinfunction "QO0_49") (pintype "passive+no_connect"))
    )
    (net (code "103") (name "unconnected-(U1-QO1-Pad50)") (class "Default")
      (node (ref "U1") (pin "50") (pinfunction "QO1_50") (pintype "passive+no_connect"))
    )
    (net (code "104") (name "unconnected-(U1-QO2-Pad51)") (class "Default")
      (node (ref "U1") (pin "51") (pinfunction "QO2_51") (pintype "passive+no_connect"))
    )
    (net (code "105") (name "unconnected-(U1-QO3-Pad52)") (class "Default")
      (node (ref "U1") (pin "52") (pinfunction "QO3_52") (pintype "passive+no_connect"))
    )
    (net (code "106") (name "unconnected-(U1-QO4-Pad53)") (class "Default")
      (node (ref "U1") (pin "53") (pinfunction "QO4_53") (pintype "passive+no_connect"))
    )
    (net (code "107") (name "unconnected-(U1-QO5-Pad54)") (class "Default")
      (node (ref "U1") (pin "54") (pinfunction "QO5_54") (pintype "passive+no_connect"))
    )
    (net (code "108") (name "unconnected-(U1-QO6-Pad55)") (class "Default")
      (node (ref "U1") (pin "55") (pinfunction "QO6_55") (pintype "passive+no_connect"))
    )
    (net (code "109") (name "unconnected-(U1-QO7-Pad56)") (class "Default")
      (node (ref "U1") (pin "56") (pinfunction "QO7_56") (pintype "passive+no_connect"))
    )
    (net (code "110") (name "unconnected-(U1-QO8-Pad59)") (class "Default")
      (node (ref "U1") (pin "59") (pinfunction "QO8_59") (pintype "passive+no_connect"))
    )
    (net (code "111") (name "unconnected-(U1-QO9-Pad60)") (class "Default")
      (node (ref "U1") (pin "60") (pinfunction "QO9_60") (pintype "passive+no_connect"))
    )
    (net (code "112") (name "unconnected-(U1-QO10-Pad61)") (class "Default")
      (node (ref "U1") (pin "61") (pinfunction "QO10_61") (pintype "passive+no_connect"))
    )
    (net (code "113") (name "unconnected-(U1-QO11-Pad62)") (class "Default")
      (node (ref "U1") (pin "62") (pinfunction "QO11_62") (pintype "passive+no_connect"))
    )
    (net (code "114") (name "unconnected-(U1-QO12-Pad63)") (class "Default")
      (node (ref "U1") (pin "63") (pinfunction "QO12_63") (pintype "passive+no_connect"))
    )
    (net (code "115") (name "unconnected-(U1-QO13-Pad64)") (class "Default")
      (node (ref "U1") (pin "64") (pinfunction "QO13_64") (pintype "passive+no_connect"))
    )
    (net (code "116") (name "unconnected-(U1-QO14-Pad65)") (class "Default")
      (node (ref "U1") (pin "65") (pinfunction "QO14_65") (pintype "passive+no_connect"))
    )
    (net (code "117") (name "unconnected-(U1-QO15-Pad66)") (class "Default")
      (node (ref "U1") (pin "66") (pinfunction "QO15_66") (pintype "passive+no_connect"))
    )
    (net (code "118") (name "unconnected-(U1-QO16-Pad69)") (class "Default")
      (node (ref "U1") (pin "69") (pinfunction "QO16_69") (pintype "passive+no_connect"))
    )
    (net (code "119") (name "unconnected-(U1-QO17-Pad70)") (class "Default")
      (node (ref "U1") (pin "70") (pinfunction "QO17_70") (pintype "passive+no_connect"))
    )
    (net (code "120") (name "unconnected-(U1-QO18-Pad71)") (class "Default")
      (node (ref "U1") (pin "71") (pinfunction "QO18_71") (pintype "passive+no_connect"))
    )
    (net (code "121") (name "unconnected-(U1-QO19-Pad72)") (class "Default")
      (node (ref "U1") (pin "72") (pinfunction "QO19_72") (pintype "passive+no_connect"))
    )
    (net (code "122") (name "unconnected-(U1-QO20-Pad73)") (class "Default")
      (node (ref "U1") (pin "73") (pinfunction "QO20_73") (pintype "passive+no_connect"))
    )
    (net (code "123") (name "unconnected-(U1-QO21-Pad74)") (class "Default")
      (node (ref "U1") (pin "74") (pinfunction "QO21_74") (pintype "passive+no_connect"))
    )
    (net (code "124") (name "unconnected-(U1-QO22-Pad75)") (class "Default")
      (node (ref "U1") (pin "75") (pinfunction "QO22_75") (pintype "passive+no_connect"))
    )
    (net (code "125") (name "unconnected-(U1-QO23-Pad77)") (class "Default")
      (node (ref "U1") (pin "77") (pinfunction "QO23_77") (pintype "passive+no_connect"))
    )
    (net (code "126") (name "unconnected-(U1-SCDT-Pad8)") (class "Default")
      (node (ref "U1") (pin "8") (pinfunction "SCDT_8") (pintype "passive+no_connect"))
    )
    (net (code "127") (name "unconnected-(U1-~{PDO}-Pad9)") (class "Default")
      (node (ref "U1") (pin "9") (pinfunction "~{PDO}_9") (pintype "passive+no_connect"))
    )
    (net (code "128") (name "unconnected-(U1-~{PD}-Pad2)") (class "Default")
      (node (ref "U1") (pin "2") (pinfunction "~{PD}_2") (pintype "passive+no_connect"))
    )
    (net (code "129") (name "unconnected-(X10-Blue-PadC3)") (class "Default")
      (node (ref "X10") (pin "C3") (pinfunction "Blue_C3") (pintype "passive+no_connect"))
    )
    (net (code "130") (name "unconnected-(X10-Data_3_+-Pad13)") (class "Default")
      (node (ref "X10") (pin "13") (pinfunction "Data_3_+_13") (pintype "passive+no_connect"))
    )
    (net (code "131") (name "unconnected-(X10-Data_3_--Pad12)") (class "Default")
      (node (ref "X10") (pin "12") (pinfunction "Data_3_-_12") (pintype "passive+no_connect"))
    )
    (net (code "132") (name "unconnected-(X10-Data_4_+-Pad5)") (class "Default")
      (node (ref "X10") (pin "5") (pinfunction "Data_4_+_5") (pintype "passive+no_connect"))
    )
    (net (code "133") (name "unconnected-(X10-Data_4_--Pad4)") (class "Default")
      (node (ref "X10") (pin "4") (pinfunction "Data_4_-_4") (pintype "passive+no_connect"))
    )
    (net (code "134") (name "unconnected-(X10-Data_5_+-Pad21)") (class "Default")
      (node (ref "X10") (pin "21") (pinfunction "Data_5_+_21") (pintype "passive+no_connect"))
    )
    (net (code "135") (name "unconnected-(X10-Data_5_--Pad20)") (class "Default")
      (node (ref "X10") (pin "20") (pinfunction "Data_5_-_20") (pintype "passive+no_connect"))
    )
    (net (code "136") (name "unconnected-(X10-Green-PadC2)") (class "Default")
      (node (ref "X10") (pin "C2") (pinfunction "Green_C2") (pintype "passive+no_connect"))
    )
    (net (code "137") (name "unconnected-(X10-H-Sync-PadC4)") (class "Default")
      (node (ref "X10") (pin "C4") (pinfunction "H-Sync_C4") (pintype "passive+no_connect"))
    )
    (net (code "138") (name "unconnected-(X10-Red-PadC1)") (class "Default")
      (node (ref "X10") (pin "C1") (pinfunction "Red_C1") (pintype "passive+no_connect"))
    )
    (net (code "139") (name "unconnected-(X10-V-Sync-Pad8)") (class "Default")
      (node (ref "X10") (pin "8") (pinfunction "V-Sync_8") (pintype "passive+no_connect"))
    )
  )
)
